# Ancillaries.net
KiCad netlist of a schematic drawn in Altium Designer
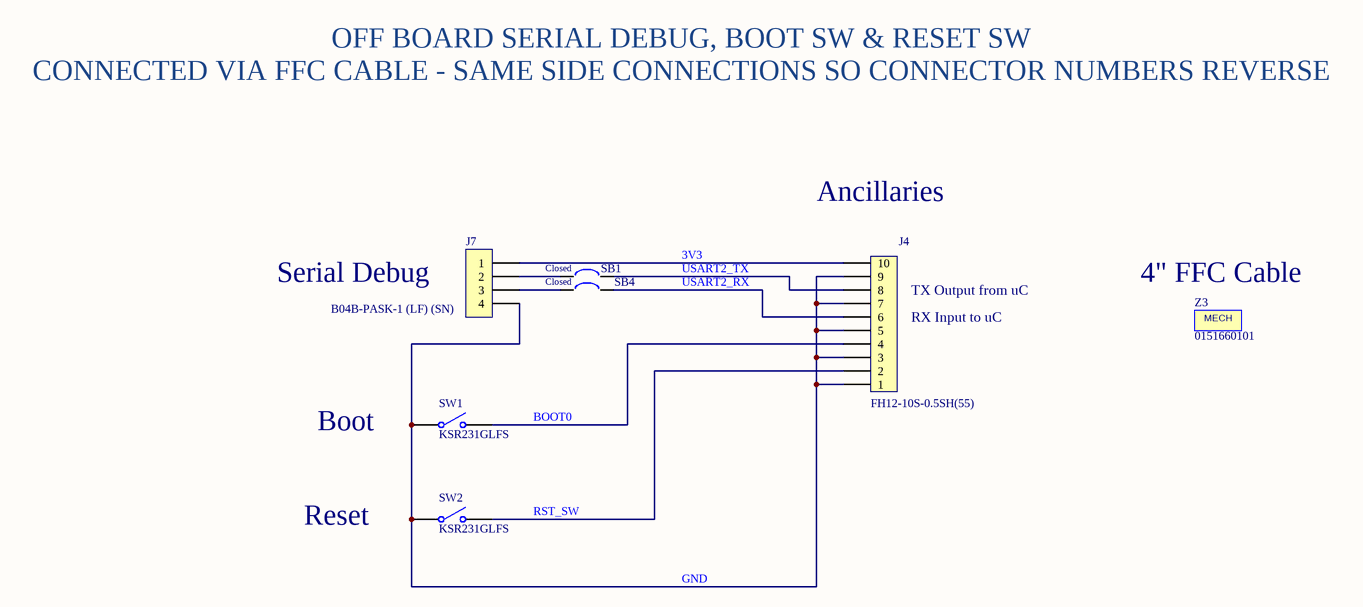
[diagram p0: Ancillaries.SchDoc]

(export (version "E")
  (design (tool "Eeschema 10.0.6"))
  (components
    (comp (ref "J4")
      (value "Ancillaries")
      (footprint "FH12-10S-0_5SH")
      (description "Connector 10W FFC/FPC 0.5mm SM ZIF")
      (fields (field (name "MANUPARTNO") "FH12-10S-0.5SH(55)") (field (name "MANUFACTURER") "Hirose"))
      (libsource (lib "Library") (part "CON10"))
    )
    (comp (ref "J7")
      (value "Serial Debug")
      (footprint "B04B-PASK-1")
      (description "Connector 4 Way Vertical JST B04B-PASK-1 (LF) (SN) 2mm Pitch")
      (fields (field (name "MANUPARTNO") "B04B-PASK-1 (LF) (SN)") (field (name "MANUFACTURER") "JST"))
      (libsource (lib "Library") (part "CON4"))
    )
    (comp (ref "SB1")
      (value "Solder Blob Closed")
      (footprint "0603SolderLinkClosed")
      (description "Solder Blob - Closed 0603 SM pads")
      (libsource (lib "Library") (part "Solder Blob Closed"))
    )
    (comp (ref "SB4")
      (value "Solder Blob Closed")
      (footprint "0603SolderLinkClosed")
      (description "Solder Blob - Closed 0603 SM pads")
      (libsource (lib "Library") (part "Solder Blob Closed"))
    )
    (comp (ref "SW1")
      (value "Boot")
      (footprint "SW_KSR")
      (description "Switch SMD SPST-NO Vertical ITT/Cannon KSR231GLFS")
      (fields (field (name "MANUPARTNO") "KSR231GLFS") (field (name "MANUFACTURER") "ITT/Cannon"))
      (libsource (lib "Library") (part "SPST"))
    )
    (comp (ref "SW2")
      (value "Reset")
      (footprint "SW_KSR")
      (description "Switch SMD SPST-NO Vertical ITT/Cannon KSR231GLFS")
      (fields (field (name "MANUPARTNO") "KSR231GLFS") (field (name "MANUFACTURER") "ITT/Cannon"))
      (libsource (lib "Library") (part "SPST"))
    )
    (comp (ref "Z3")
      (value "4\" FFC Cable")
      (description "CABLE FFC/FPC 10POS 0.5MM 4\"")
      (fields (field (name "MANUPARTNO") "0151660101") (field (name "MANUFACTURER") "Molex"))
      (libsource (lib "Library") (part "MECH"))
    )
  )
  (nets
    (net (code "1") (name "Net-(J4-Pad6)") (class "Default")
      (node (ref "J4") (pin "6") (pinfunction "6_6") (pintype "passive"))
      (node (ref "SB4") (pin "2") (pinfunction "2_2") (pintype "passive"))
    )
    (net (code "2") (name "Net-(J4-Pad8)") (class "Default")
      (node (ref "J4") (pin "8") (pinfunction "8_8") (pintype "passive"))
      (node (ref "SB1") (pin "2") (pinfunction "2_2") (pintype "passive"))
    )
    (net (code "3") (name "Net-(J4-Pad10)") (class "Default")
      (node (ref "J4") (pin "10") (pinfunction "10_10") (pintype "passive"))
      (node (ref "J7") (pin "1") (pinfunction "1_1") (pintype "passive"))
    )
    (net (code "4") (name "Net-(J7-Pad2)") (class "Default")
      (node (ref "J7") (pin "2") (pinfunction "2_2") (pintype "passive"))
      (node (ref "SB1") (pin "1") (pinfunction "1_1") (pintype "passive"))
    )
    (net (code "5") (name "Net-(J7-Pad3)") (class "Default")
      (node (ref "J7") (pin "3") (pinfunction "3_3") (pintype "passive"))
      (node (ref "SB4") (pin "1") (pinfunction "1_1") (pintype "passive"))
    )
    (net (code "6") (name "Net-(SW1-COMMON)") (class "Default")
      (node (ref "J4") (pin "1") (pinfunction "1_1") (pintype "passive"))
      (node (ref "J4") (pin "3") (pinfunction "3_3") (pintype "passive"))
      (node (ref "J4") (pin "5") (pinfunction "5_5") (pintype "passive"))
      (node (ref "J4") (pin "7") (pinfunction "7_7") (pintype "passive"))
      (node (ref "J4") (pin "9") (pinfunction "9_9") (pintype "passive"))
      (node (ref "J7") (pin "4") (pinfunction "4_4") (pintype "passive"))
      (node (ref "SW1") (pin "1") (pinfunction "COMMON_1") (pintype "passive"))
      (node (ref "SW2") (pin "1") (pinfunction "COMMON_1") (pintype "passive"))
    )
    (net (code "7") (name "Net-(SW1-NO)") (class "Default")
      (node (ref "J4") (pin "4") (pinfunction "4_4") (pintype "passive"))
      (node (ref "SW1") (pin "2") (pinfunction "NO_2") (pintype "passive"))
    )
    (net (code "8") (name "Net-(SW2-NO)") (class "Default")
      (node (ref "J4") (pin "2") (pinfunction "2_2") (pintype "passive"))
      (node (ref "SW2") (pin "2") (pinfunction "NO_2") (pintype "passive"))
    )
  )
)
